# MDL-485.net
KiCad netlist of a schematic drawn in Altium Designer
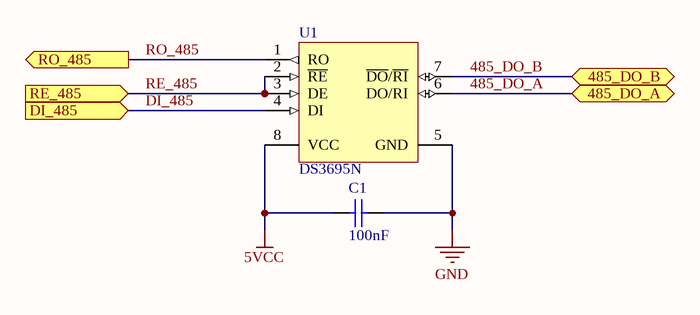
[diagram p0: MDL-485.SchDoc]

(export (version "E")
  (design (tool "Eeschema 10.0.6"))
  (components
    (comp (ref "C1")
      (value "100nF")
      (footprint "VP44-2.5")
      (description "Dipped Radial Multilayer Ceramic Capacitor X7R: 220nF, 100V")
      (fields (field (name "Comment") "VP44BY224JB") (field (name "PUBLISHER") "Altium Limited"))
      (libsource (lib "Vishay Vitramon Ceramic Dipped Capacitor") (part "VP44BY224JB"))
    )
    (comp (ref "U1")
      (value "DS3695N")
      (footprint "N08E")
      (description "Multipoint RS485/RS422 Transceiver/Repeater")
      (fields
        (field (name "MANUFACTURER") "National Semiconductor")
        (field (name "DIGIKEYPARTNUMBER") "DS3695N-ND")
        (field (name "PUBLISHER") "Altium Limited")
      )
      (libsource (lib "NSC Interface") (part "DS3695N"))
    )
  )
  (nets
    (net (code "1") (name "/485_DO_A") (class "Default")
      (node (ref "U1") (pin "6") (pinfunction "DO/RI_6") (pintype "bidirectional"))
    )
    (net (code "2") (name "/485_DO_B") (class "Default")
      (node (ref "U1") (pin "7") (pinfunction "~{DO}/~{RI}_7") (pintype "bidirectional"))
    )
    (net (code "3") (name "/DI_485") (class "Default")
      (node (ref "U1") (pin "4") (pinfunction "DI_4") (pintype "input"))
    )
    (net (code "4") (name "/RE_485") (class "Default")
      (node (ref "U1") (pin "2") (pinfunction "~{RE}_2") (pintype "input"))
      (node (ref "U1") (pin "3") (pinfunction "DE_3") (pintype "input"))
    )
    (net (code "5") (name "/RO_485") (class "Default")
      (node (ref "U1") (pin "1") (pinfunction "RO_1") (pintype "output"))
    )
    (net (code "6") (name "5VCC") (class "Default")
      (node (ref "C1") (pin "1") (pinfunction "1_1") (pintype "passive"))
      (node (ref "U1") (pin "8") (pinfunction "VCC_8") (pintype "power_in"))
    )
    (net (code "7") (name "GND") (class "Default")
      (node (ref "C1") (pin "2") (pinfunction "2_2") (pintype "passive"))
      (node (ref "U1") (pin "5") (pinfunction "GND_5") (pintype "power_in"))
    )
  )
)
